# Driver.net
KiCad netlist of a schematic drawn in EAGLE
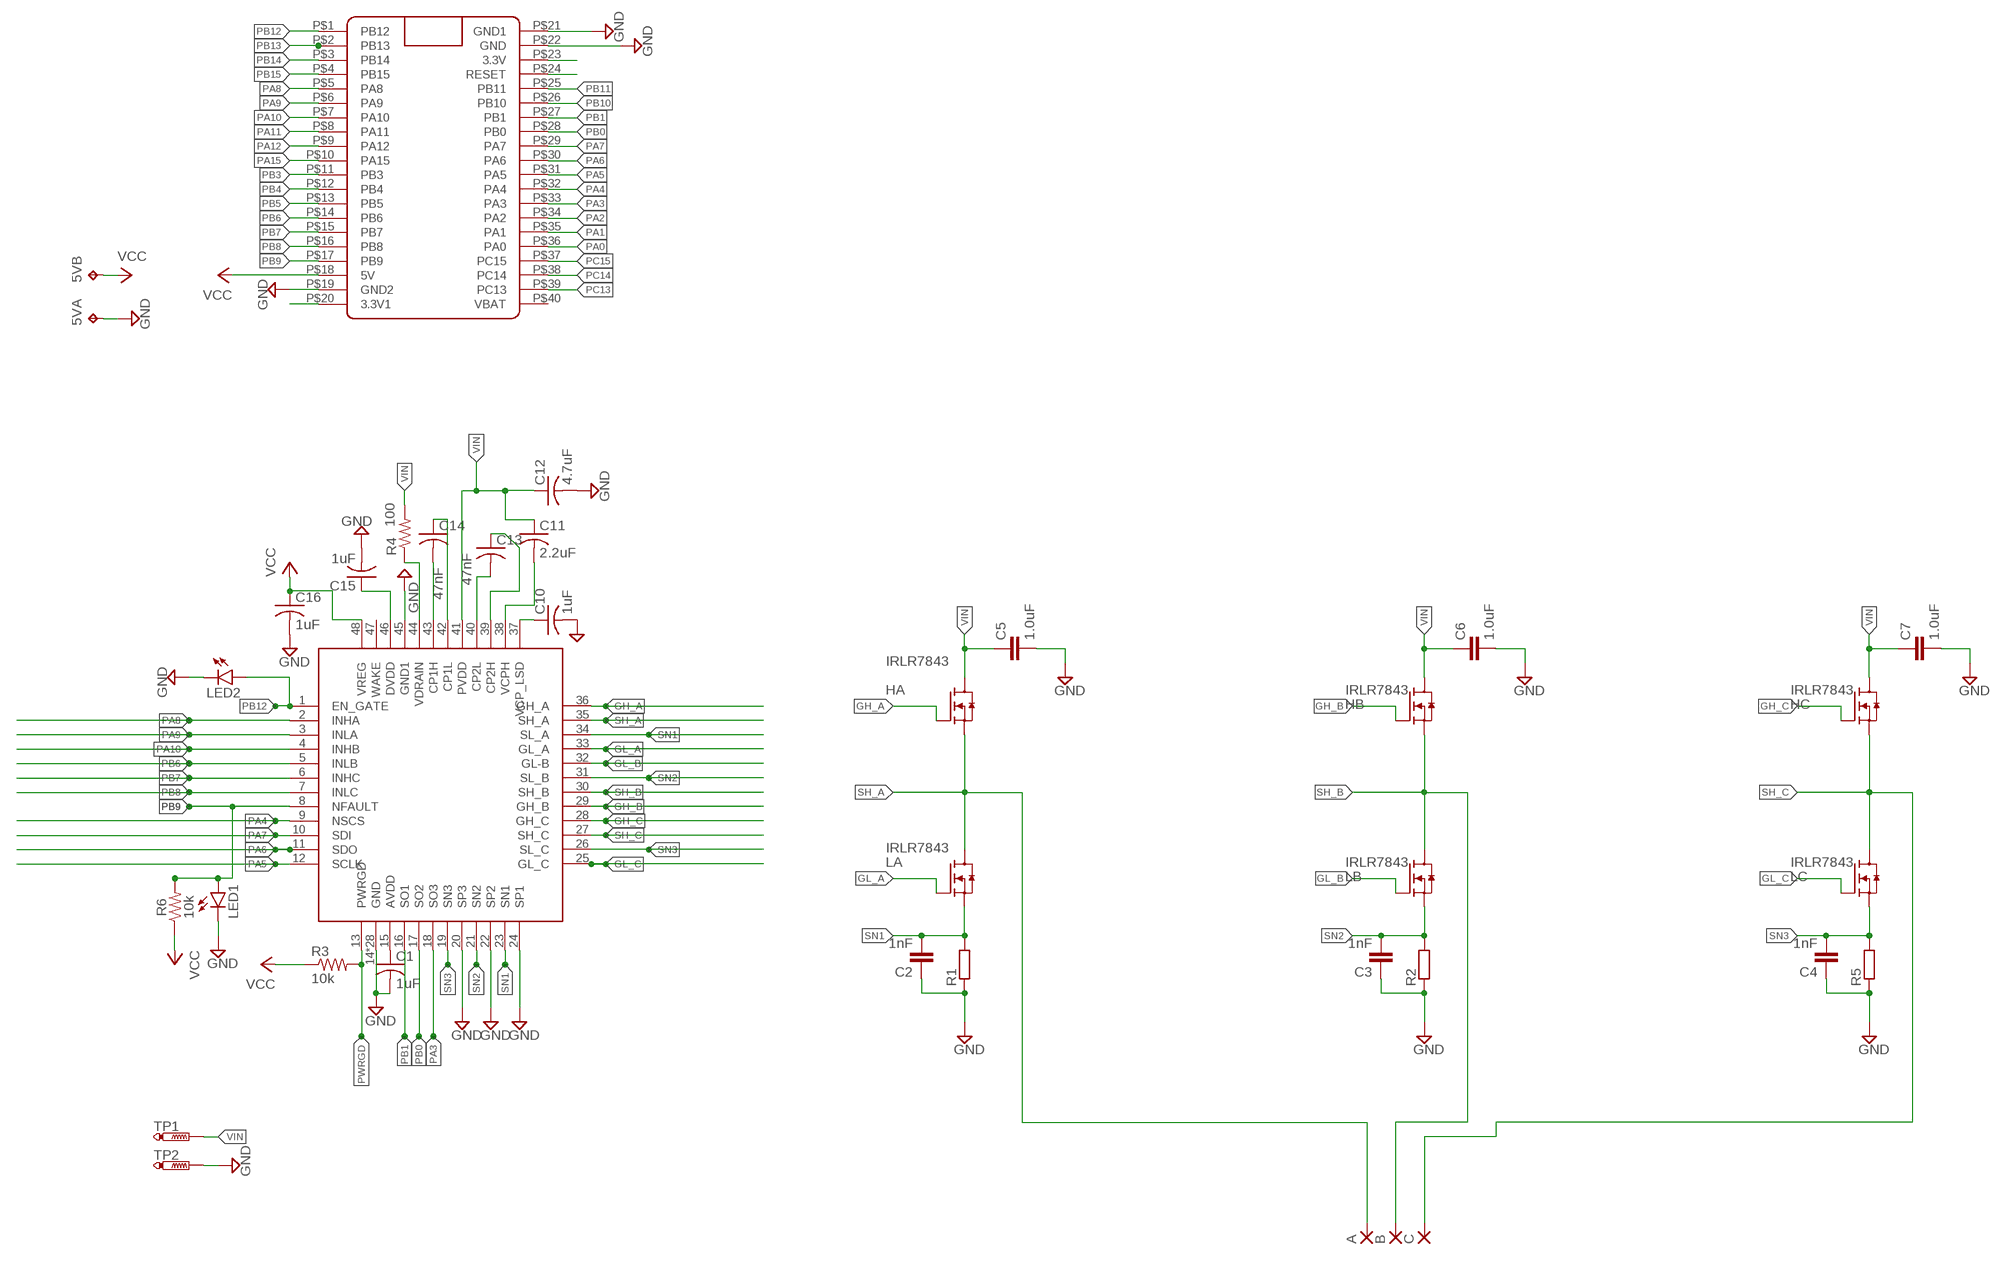
[diagram p0: schematic, sheet 1]

(export (version "E")
  (design (tool "Eeschema 10.0.6"))
  (components
    (comp (ref "5V")
      (value "TP2P2-38-17")
      (footprint "eagle-import:P2-38-17")
      (libsource (lib "eagle-import") (part "TP2P2-38-17"))
    )
    (comp (ref "A")
      (value "SMD5")
      (footprint "eagle-import:SMD2,54-5,08")
      (libsource (lib "eagle-import") (part "SMD5"))
    )
    (comp (ref "B")
      (value "SMD5")
      (footprint "eagle-import:SMD2,54-5,08")
      (libsource (lib "eagle-import") (part "SMD5"))
    )
    (comp (ref "C")
      (value "SMD5")
      (footprint "eagle-import:SMD2,54-5,08")
      (libsource (lib "eagle-import") (part "SMD5"))
    )
    (comp (ref "C1")
      (value "1uF")
      (footprint "eagle-import:C0603")
      (libsource (lib "eagle-import") (part "C-USC0603"))
    )
    (comp (ref "C2")
      (value "1nF")
      (footprint "eagle-import:0603")
      (libsource (lib "eagle-import") (part "1.0NF/1000PF-0603-50V-10%"))
    )
    (comp (ref "C3")
      (value "1nF")
      (footprint "eagle-import:0603")
      (libsource (lib "eagle-import") (part "1.0NF/1000PF-0603-50V-10%"))
    )
    (comp (ref "C4")
      (value "1nF")
      (footprint "eagle-import:0603")
      (libsource (lib "eagle-import") (part "1.0NF/1000PF-0603-50V-10%"))
    )
    (comp (ref "C5")
      (value "1.0uF")
      (footprint "eagle-import:0603")
      (libsource (lib "eagle-import") (part "1.0UF-0603-16V-10%-X7R"))
    )
    (comp (ref "C6")
      (value "1.0uF")
      (footprint "eagle-import:0603")
      (libsource (lib "eagle-import") (part "1.0UF-0603-16V-10%-X7R"))
    )
    (comp (ref "C7")
      (value "1.0uF")
      (footprint "eagle-import:0603")
      (libsource (lib "eagle-import") (part "1.0UF-0603-16V-10%-X7R"))
    )
    (comp (ref "C10")
      (value "1uF")
      (footprint "eagle-import:C0603")
      (libsource (lib "eagle-import") (part "C-USC0603"))
    )
    (comp (ref "C11")
      (value "2.2uF")
      (footprint "eagle-import:C0603")
      (libsource (lib "eagle-import") (part "C-USC0603"))
    )
    (comp (ref "C12")
      (value "4.7uF")
      (footprint "eagle-import:C0603")
      (libsource (lib "eagle-import") (part "C-USC0603"))
    )
    (comp (ref "C13")
      (value "47nF")
      (footprint "eagle-import:C0603")
      (libsource (lib "eagle-import") (part "C-USC0603"))
    )
    (comp (ref "C14")
      (value "47nF")
      (footprint "eagle-import:C0603")
      (libsource (lib "eagle-import") (part "C-USC0603"))
    )
    (comp (ref "C15")
      (value "1uF")
      (footprint "eagle-import:C0603")
      (libsource (lib "eagle-import") (part "C-USC0603"))
    )
    (comp (ref "C16")
      (value "1uF")
      (footprint "eagle-import:C0603")
      (libsource (lib "eagle-import") (part "C-USC0603"))
    )
    (comp (ref "HA")
      (value "IRLR7843")
      (footprint "eagle-import:TO252")
      (libsource (lib "eagle-import") (part "IRLR7843"))
    )
    (comp (ref "HB")
      (value "IRLR7843")
      (footprint "eagle-import:TO252")
      (libsource (lib "eagle-import") (part "IRLR7843"))
    )
    (comp (ref "HC")
      (value "IRLR7843")
      (footprint "eagle-import:TO252")
      (libsource (lib "eagle-import") (part "IRLR7843"))
    )
    (comp (ref "LA")
      (value "IRLR7843")
      (footprint "eagle-import:TO252")
      (libsource (lib "eagle-import") (part "IRLR7843"))
    )
    (comp (ref "LB")
      (value "IRLR7843")
      (footprint "eagle-import:TO252")
      (libsource (lib "eagle-import") (part "IRLR7843"))
    )
    (comp (ref "LC")
      (value "IRLR7843")
      (footprint "eagle-import:TO252")
      (libsource (lib "eagle-import") (part "IRLR7843"))
    )
    (comp (ref "LED1")
      (value "LEDCHIPLED_0805")
      (footprint "eagle-import:CHIPLED_0805")
      (libsource (lib "eagle-import") (part "LEDCHIPLED_0805"))
    )
    (comp (ref "LED2")
      (value "LEDCHIPLED_0805")
      (footprint "eagle-import:CHIPLED_0805")
      (libsource (lib "eagle-import") (part "LEDCHIPLED_0805"))
    )
    (comp (ref "R1")
      (value "R-EU_R2512")
      (footprint "eagle-import:R2512")
      (libsource (lib "eagle-import") (part "R-EU_R2512"))
    )
    (comp (ref "R2")
      (value "R-EU_R2512")
      (footprint "eagle-import:R2512")
      (libsource (lib "eagle-import") (part "R-EU_R2512"))
    )
    (comp (ref "R3")
      (value "10k")
      (footprint "eagle-import:R0603")
      (libsource (lib "eagle-import") (part "R-US_R0603"))
    )
    (comp (ref "R4")
      (value "100")
      (footprint "eagle-import:R0603")
      (libsource (lib "eagle-import") (part "R-US_R0603"))
    )
    (comp (ref "R5")
      (value "R-EU_R2512")
      (footprint "eagle-import:R2512")
      (libsource (lib "eagle-import") (part "R-EU_R2512"))
    )
    (comp (ref "R6")
      (value "10k")
      (footprint "eagle-import:0603")
      (libsource (lib "eagle-import") (part "10KOHM-0603-1/10W-1%"))
    )
    (comp (ref "TP1")
      (value "PTR1PAD1-20Y")
      (footprint "eagle-import:P1-20Y")
      (libsource (lib "eagle-import") (part "PTR1PAD1-20Y"))
    )
    (comp (ref "TP2")
      (value "PTR1PAD1-20Y")
      (footprint "eagle-import:P1-20Y")
      (libsource (lib "eagle-import") (part "PTR1PAD1-20Y"))
    )
    (comp (ref "U$1")
      (value "BLUE_PILLADVANCED")
      (footprint "eagle-import:BLUE_PILL_ADV")
      (libsource (lib "eagle-import") (part "BLUE_PILLADVANCED"))
    )
    (comp (ref "U$3")
      (value "DRV8305")
      (footprint "eagle-import:PFB_S-PQFP-G48")
      (libsource (lib "eagle-import") (part "DRV8305"))
    )
  )
  (nets
    (net (code "1") (name "GH_A") (class "Default")
      (node (ref "HA") (pin "1") (pinfunction "G_1") (pintype "passive"))
      (node (ref "U$3") (pin "36") (pinfunction "GH_A_36") (pintype "bidirectional"))
    )
    (net (code "2") (name "GH_B") (class "Default")
      (node (ref "HB") (pin "1") (pinfunction "G_1") (pintype "passive"))
      (node (ref "U$3") (pin "29") (pinfunction "GH_B_29") (pintype "bidirectional"))
    )
    (net (code "3") (name "GH_C") (class "Default")
      (node (ref "HC") (pin "1") (pinfunction "G_1") (pintype "passive"))
      (node (ref "U$3") (pin "28") (pinfunction "GH_C_28") (pintype "bidirectional"))
    )
    (net (code "4") (name "GL_A") (class "Default")
      (node (ref "LA") (pin "1") (pinfunction "G_1") (pintype "passive"))
      (node (ref "U$3") (pin "33") (pinfunction "GL_A_33") (pintype "bidirectional"))
    )
    (net (code "5") (name "GL_B") (class "Default")
      (node (ref "LB") (pin "1") (pinfunction "G_1") (pintype "passive"))
      (node (ref "U$3") (pin "32") (pinfunction "GL-B_32") (pintype "bidirectional"))
    )
    (net (code "6") (name "GL_C") (class "Default")
      (node (ref "LC") (pin "1") (pinfunction "G_1") (pintype "passive"))
      (node (ref "U$3") (pin "25") (pinfunction "GL_C_25") (pintype "bidirectional"))
    )
    (net (code "7") (name "GND") (class "Default")
      (node (ref "5V") (pin "TP-1") (pinfunction "TP_TP-1") (pintype "input"))
      (node (ref "C1") (pin "2") (pinfunction "2_2") (pintype "passive"))
      (node (ref "C10") (pin "2") (pinfunction "2_2") (pintype "passive"))
      (node (ref "C12") (pin "2") (pinfunction "2_2") (pintype "passive"))
      (node (ref "C15") (pin "2") (pinfunction "2_2") (pintype "passive"))
      (node (ref "C16") (pin "2") (pinfunction "2_2") (pintype "passive"))
      (node (ref "C2") (pin "1") (pinfunction "1_1") (pintype "passive"))
      (node (ref "C3") (pin "1") (pinfunction "1_1") (pintype "passive"))
      (node (ref "C4") (pin "1") (pinfunction "1_1") (pintype "passive"))
      (node (ref "C5") (pin "2") (pinfunction "2_2") (pintype "passive"))
      (node (ref "C6") (pin "2") (pinfunction "2_2") (pintype "passive"))
      (node (ref "C7") (pin "2") (pinfunction "2_2") (pintype "passive"))
      (node (ref "LED1") (pin "C") (pinfunction "C_C") (pintype "passive"))
      (node (ref "LED2") (pin "C") (pinfunction "C_C") (pintype "passive"))
      (node (ref "R1") (pin "1") (pinfunction "1_1") (pintype "passive"))
      (node (ref "R2") (pin "1") (pinfunction "1_1") (pintype "passive"))
      (node (ref "R5") (pin "1") (pinfunction "1_1") (pintype "passive"))
      (node (ref "TP2") (pin "TP") (pinfunction "TP_TP") (pintype "input"))
      (node (ref "U$1") (pin "P$19") (pinfunction "GND2_P$19") (pintype "bidirectional"))
      (node (ref "U$1") (pin "P$21") (pinfunction "GND1_P$21") (pintype "power_in"))
      (node (ref "U$1") (pin "P$22") (pinfunction "GND_P$22") (pintype "bidirectional"))
      (node (ref "U$3") (pin "14") (pinfunction "GND_14") (pintype "bidirectional"))
      (node (ref "U$3") (pin "20") (pinfunction "SP3_20") (pintype "bidirectional"))
      (node (ref "U$3") (pin "22") (pinfunction "SP2_22") (pintype "bidirectional"))
      (node (ref "U$3") (pin "24") (pinfunction "SP1_24") (pintype "bidirectional"))
      (node (ref "U$3") (pin "45") (pinfunction "GND1_45") (pintype "bidirectional"))
      (node (ref "U$3") (pin "P$1") (pinfunction "GND_P$1") (pintype "bidirectional"))
      (node (ref "U$3") (pin "P$10") (pinfunction "GND_P$10") (pintype "bidirectional"))
      (node (ref "U$3") (pin "P$11") (pinfunction "GND_P$11") (pintype "bidirectional"))
      (node (ref "U$3") (pin "P$12") (pinfunction "GND_P$12") (pintype "bidirectional"))
      (node (ref "U$3") (pin "P$13") (pinfunction "GND_P$13") (pintype "bidirectional"))
      (node (ref "U$3") (pin "P$14") (pinfunction "GND_P$14") (pintype "bidirectional"))
      (node (ref "U$3") (pin "P$15") (pinfunction "GND_P$15") (pintype "bidirectional"))
      (node (ref "U$3") (pin "P$16") (pinfunction "GND_P$16") (pintype "bidirectional"))
      (node (ref "U$3") (pin "P$17") (pinfunction "GND_P$17") (pintype "bidirectional"))
      (node (ref "U$3") (pin "P$18") (pinfunction "GND_P$18") (pintype "bidirectional"))
      (node (ref "U$3") (pin "P$19") (pinfunction "GND_P$19") (pintype "bidirectional"))
      (node (ref "U$3") (pin "P$2") (pinfunction "GND_P$2") (pintype "bidirectional"))
      (node (ref "U$3") (pin "P$20") (pinfunction "GND_P$20") (pintype "bidirectional"))
      (node (ref "U$3") (pin "P$21") (pinfunction "GND_P$21") (pintype "bidirectional"))
      (node (ref "U$3") (pin "P$22") (pinfunction "GND_P$22") (pintype "bidirectional"))
      (node (ref "U$3") (pin "P$23") (pinfunction "GND_P$23") (pintype "bidirectional"))
      (node (ref "U$3") (pin "P$24") (pinfunction "GND_P$24") (pintype "bidirectional"))
      (node (ref "U$3") (pin "P$25") (pinfunction "GND_P$25") (pintype "bidirectional"))
      (node (ref "U$3") (pin "P$26") (pinfunction "GND_P$26") (pintype "bidirectional"))
      (node (ref "U$3") (pin "P$27") (pinfunction "GND_P$27") (pintype "bidirectional"))
      (node (ref "U$3") (pin "P$3") (pinfunction "GND_P$3") (pintype "bidirectional"))
      (node (ref "U$3") (pin "P$4") (pinfunction "GND_P$4") (pintype "bidirectional"))
      (node (ref "U$3") (pin "P$5") (pinfunction "GND_P$5") (pintype "bidirectional"))
      (node (ref "U$3") (pin "P$6") (pinfunction "GND_P$6") (pintype "bidirectional"))
      (node (ref "U$3") (pin "P$7") (pinfunction "GND_P$7") (pintype "bidirectional"))
      (node (ref "U$3") (pin "P$8") (pinfunction "GND_P$8") (pintype "bidirectional"))
      (node (ref "U$3") (pin "P$9") (pinfunction "GND_P$9") (pintype "bidirectional"))
    )
    (net (code "8") (name "Net-(U$3-AVDD)") (class "Default")
      (node (ref "C1") (pin "1") (pinfunction "1_1") (pintype "passive"))
      (node (ref "U$3") (pin "15") (pinfunction "AVDD_15") (pintype "bidirectional"))
    )
    (net (code "9") (name "Net-(U$3-CP1H)") (class "Default")
      (node (ref "C14") (pin "2") (pinfunction "2_2") (pintype "passive"))
      (node (ref "U$3") (pin "43") (pinfunction "CP1H_43") (pintype "bidirectional"))
    )
    (net (code "10") (name "Net-(U$3-CP1L)") (class "Default")
      (node (ref "C14") (pin "1") (pinfunction "1_1") (pintype "passive"))
      (node (ref "U$3") (pin "42") (pinfunction "CP1L_42") (pintype "bidirectional"))
    )
    (net (code "11") (name "Net-(U$3-CP2H)") (class "Default")
      (node (ref "C13") (pin "1") (pinfunction "1_1") (pintype "passive"))
      (node (ref "U$3") (pin "39") (pinfunction "CP2H_39") (pintype "bidirectional"))
    )
    (net (code "12") (name "Net-(U$3-CP2L)") (class "Default")
      (node (ref "C13") (pin "2") (pinfunction "2_2") (pintype "passive"))
      (node (ref "U$3") (pin "40") (pinfunction "CP2L_40") (pintype "bidirectional"))
    )
    (net (code "13") (name "Net-(U$3-DVDD)") (class "Default")
      (node (ref "C15") (pin "1") (pinfunction "1_1") (pintype "passive"))
      (node (ref "U$3") (pin "46") (pinfunction "DVDD_46") (pintype "bidirectional"))
    )
    (net (code "14") (name "Net-(U$3-VCPH)") (class "Default")
      (node (ref "C11") (pin "2") (pinfunction "2_2") (pintype "passive"))
      (node (ref "U$3") (pin "38") (pinfunction "VCPH_38") (pintype "bidirectional"))
    )
    (net (code "15") (name "Net-(U$3-VCP_LSD)") (class "Default")
      (node (ref "C10") (pin "1") (pinfunction "1_1") (pintype "passive"))
      (node (ref "U$3") (pin "37") (pinfunction "VCP_LSD_37") (pintype "bidirectional"))
    )
    (net (code "16") (name "Net-(U$3-VDRAIN)") (class "Default")
      (node (ref "R4") (pin "1") (pinfunction "1_1") (pintype "passive"))
      (node (ref "U$3") (pin "44") (pinfunction "VDRAIN_44") (pintype "bidirectional"))
    )
    (net (code "17") (name "PA0") (class "Default")
      (node (ref "U$1") (pin "P$36") (pinfunction "PA0_P$36") (pintype "bidirectional"))
    )
    (net (code "18") (name "PA1") (class "Default")
      (node (ref "U$1") (pin "P$35") (pinfunction "PA1_P$35") (pintype "bidirectional"))
    )
    (net (code "19") (name "PA2") (class "Default")
      (node (ref "U$1") (pin "P$34") (pinfunction "PA2_P$34") (pintype "bidirectional"))
    )
    (net (code "20") (name "PA3") (class "Default")
      (node (ref "U$1") (pin "P$33") (pinfunction "PA3_P$33") (pintype "bidirectional"))
      (node (ref "U$3") (pin "18") (pinfunction "SO3_18") (pintype "bidirectional"))
    )
    (net (code "21") (name "PA4") (class "Default")
      (node (ref "U$1") (pin "P$32") (pinfunction "PA4_P$32") (pintype "bidirectional"))
      (node (ref "U$3") (pin "9") (pinfunction "NSCS_9") (pintype "bidirectional"))
    )
    (net (code "22") (name "PA5") (class "Default")
      (node (ref "U$1") (pin "P$31") (pinfunction "PA5_P$31") (pintype "bidirectional"))
      (node (ref "U$3") (pin "12") (pinfunction "SCLK_12") (pintype "bidirectional"))
    )
    (net (code "23") (name "PA6") (class "Default")
      (node (ref "U$1") (pin "P$30") (pinfunction "PA6_P$30") (pintype "bidirectional"))
      (node (ref "U$3") (pin "11") (pinfunction "SDO_11") (pintype "bidirectional"))
    )
    (net (code "24") (name "PA7") (class "Default")
      (node (ref "U$1") (pin "P$29") (pinfunction "PA7_P$29") (pintype "bidirectional"))
      (node (ref "U$3") (pin "10") (pinfunction "SDI_10") (pintype "bidirectional"))
    )
    (net (code "25") (name "PA8") (class "Default")
      (node (ref "U$1") (pin "P$5") (pinfunction "PA8_P$5") (pintype "bidirectional"))
      (node (ref "U$3") (pin "2") (pinfunction "INHA_2") (pintype "bidirectional"))
    )
    (net (code "26") (name "PA9") (class "Default")
      (node (ref "U$1") (pin "P$6") (pinfunction "PA9_P$6") (pintype "bidirectional"))
      (node (ref "U$3") (pin "3") (pinfunction "INLA_3") (pintype "bidirectional"))
    )
    (net (code "27") (name "PA10") (class "Default")
      (node (ref "U$1") (pin "P$7") (pinfunction "PA10_P$7") (pintype "bidirectional"))
      (node (ref "U$3") (pin "4") (pinfunction "INHB_4") (pintype "bidirectional"))
    )
    (net (code "28") (name "PA11") (class "Default")
      (node (ref "U$1") (pin "P$8") (pinfunction "PA11_P$8") (pintype "bidirectional"))
    )
    (net (code "29") (name "PA12") (class "Default")
      (node (ref "U$1") (pin "P$9") (pinfunction "PA12_P$9") (pintype "bidirectional"))
    )
    (net (code "30") (name "PA15") (class "Default")
      (node (ref "U$1") (pin "P$10") (pinfunction "PA15_P$10") (pintype "bidirectional"))
    )
    (net (code "31") (name "PB0") (class "Default")
      (node (ref "U$1") (pin "P$28") (pinfunction "PB0_P$28") (pintype "bidirectional"))
      (node (ref "U$3") (pin "17") (pinfunction "SO2_17") (pintype "bidirectional"))
    )
    (net (code "32") (name "PB1") (class "Default")
      (node (ref "U$1") (pin "P$27") (pinfunction "PB1_P$27") (pintype "bidirectional"))
      (node (ref "U$3") (pin "16") (pinfunction "SO1_16") (pintype "bidirectional"))
    )
    (net (code "33") (name "PB3") (class "Default")
      (node (ref "U$1") (pin "P$11") (pinfunction "PB3_P$11") (pintype "bidirectional"))
    )
    (net (code "34") (name "PB4") (class "Default")
      (node (ref "U$1") (pin "P$12") (pinfunction "PB4_P$12") (pintype "bidirectional"))
    )
    (net (code "35") (name "PB5") (class "Default")
      (node (ref "U$1") (pin "P$13") (pinfunction "PB5_P$13") (pintype "bidirectional"))
    )
    (net (code "36") (name "PB6") (class "Default")
      (node (ref "U$1") (pin "P$14") (pinfunction "PB6_P$14") (pintype "bidirectional"))
      (node (ref "U$3") (pin "5") (pinfunction "INLB_5") (pintype "bidirectional"))
    )
    (net (code "37") (name "PB7") (class "Default")
      (node (ref "U$1") (pin "P$15") (pinfunction "PB7_P$15") (pintype "bidirectional"))
      (node (ref "U$3") (pin "6") (pinfunction "INHC_6") (pintype "bidirectional"))
    )
    (net (code "38") (name "PB8") (class "Default")
      (node (ref "U$1") (pin "P$16") (pinfunction "PB8_P$16") (pintype "bidirectional"))
      (node (ref "U$3") (pin "7") (pinfunction "INLC_7") (pintype "bidirectional"))
    )
    (net (code "39") (name "PB9") (class "Default")
      (node (ref "LED1") (pin "A") (pinfunction "A_A") (pintype "passive"))
      (node (ref "R6") (pin "2") (pinfunction "2_2") (pintype "passive"))
      (node (ref "U$1") (pin "P$17") (pinfunction "PB9_P$17") (pintype "bidirectional"))
      (node (ref "U$3") (pin "8") (pinfunction "NFAULT_8") (pintype "bidirectional"))
    )
    (net (code "40") (name "PB10") (class "Default")
      (node (ref "U$1") (pin "P$26") (pinfunction "PB10_P$26") (pintype "bidirectional"))
    )
    (net (code "41") (name "PB11") (class "Default")
      (node (ref "U$1") (pin "P$25") (pinfunction "PB11_P$25") (pintype "bidirectional"))
    )
    (net (code "42") (name "PB12") (class "Default")
      (node (ref "LED2") (pin "A") (pinfunction "A_A") (pintype "passive"))
      (node (ref "U$1") (pin "P$1") (pinfunction "PB12_P$1") (pintype "bidirectional"))
      (node (ref "U$3") (pin "1") (pinfunction "EN_GATE_1") (pintype "bidirectional"))
    )
    (net (code "43") (name "PB13") (class "Default")
      (node (ref "U$1") (pin "P$2") (pinfunction "PB13_P$2") (pintype "bidirectional"))
    )
    (net (code "44") (name "PB14") (class "Default")
      (node (ref "U$1") (pin "P$3") (pinfunction "PB14_P$3") (pintype "bidirectional"))
    )
    (net (code "45") (name "PB15") (class "Default")
      (node (ref "U$1") (pin "P$4") (pinfunction "PB15_P$4") (pintype "bidirectional"))
    )
    (net (code "46") (name "PC13") (class "Default")
      (node (ref "U$1") (pin "P$39") (pinfunction "PC13_P$39") (pintype "bidirectional"))
    )
    (net (code "47") (name "PC14") (class "Default")
      (node (ref "U$1") (pin "P$38") (pinfunction "PC14_P$38") (pintype "bidirectional"))
    )
    (net (code "48") (name "PC15") (class "Default")
      (node (ref "U$1") (pin "P$37") (pinfunction "PC15_P$37") (pintype "bidirectional"))
    )
    (net (code "49") (name "PWRGD") (class "Default")
      (node (ref "R3") (pin "2") (pinfunction "2_2") (pintype "passive"))
      (node (ref "U$3") (pin "13") (pinfunction "PWRGD_13") (pintype "bidirectional"))
    )
    (net (code "50") (name "SH_A") (class "Default")
      (node (ref "A") (pin "1") (pinfunction "P_1") (pintype "passive"))
      (node (ref "HA") (pin "2") (pinfunction "S_2") (pintype "passive"))
      (node (ref "LA") (pin "3") (pinfunction "D_3") (pintype "passive"))
      (node (ref "U$3") (pin "35") (pinfunction "SH_A_35") (pintype "bidirectional"))
    )
    (net (code "51") (name "SH_B") (class "Default")
      (node (ref "B") (pin "1") (pinfunction "P_1") (pintype "passive"))
      (node (ref "HB") (pin "2") (pinfunction "S_2") (pintype "passive"))
      (node (ref "LB") (pin "3") (pinfunction "D_3") (pintype "passive"))
      (node (ref "U$3") (pin "30") (pinfunction "SH_B_30") (pintype "bidirectional"))
    )
    (net (code "52") (name "SH_C") (class "Default")
      (node (ref "C") (pin "1") (pinfunction "P_1") (pintype "passive"))
      (node (ref "HC") (pin "2") (pinfunction "S_2") (pintype "passive"))
      (node (ref "LC") (pin "3") (pinfunction "D_3") (pintype "passive"))
      (node (ref "U$3") (pin "27") (pinfunction "SH_C_27") (pintype "bidirectional"))
    )
    (net (code "53") (name "SN1") (class "Default")
      (node (ref "C2") (pin "2") (pinfunction "2_2") (pintype "passive"))
      (node (ref "LA") (pin "2") (pinfunction "S_2") (pintype "passive"))
      (node (ref "R1") (pin "2") (pinfunction "2_2") (pintype "passive"))
      (node (ref "U$3") (pin "23") (pinfunction "SN1_23") (pintype "bidirectional"))
      (node (ref "U$3") (pin "34") (pinfunction "SL_A_34") (pintype "bidirectional"))
    )
    (net (code "54") (name "SN2") (class "Default")
      (node (ref "C3") (pin "2") (pinfunction "2_2") (pintype "passive"))
      (node (ref "LB") (pin "2") (pinfunction "S_2") (pintype "passive"))
      (node (ref "R2") (pin "2") (pinfunction "2_2") (pintype "passive"))
      (node (ref "U$3") (pin "21") (pinfunction "SN2_21") (pintype "bidirectional"))
      (node (ref "U$3") (pin "31") (pinfunction "SL_B_31") (pintype "bidirectional"))
    )
    (net (code "55") (name "SN3") (class "Default")
      (node (ref "C4") (pin "2") (pinfunction "2_2") (pintype "passive"))
      (node (ref "LC") (pin "2") (pinfunction "S_2") (pintype "passive"))
      (node (ref "R5") (pin "2") (pinfunction "2_2") (pintype "passive"))
      (node (ref "U$3") (pin "19") (pinfunction "SN3_19") (pintype "bidirectional"))
      (node (ref "U$3") (pin "26") (pinfunction "SL_C_26") (pintype "bidirectional"))
    )
    (net (code "56") (name "VCC") (class "Default")
      (node (ref "5V") (pin "TP-2") (pinfunction "TP_TP-2") (pintype "input"))
      (node (ref "C16") (pin "1") (pinfunction "1_1") (pintype "passive"))
      (node (ref "R3") (pin "1") (pinfunction "1_1") (pintype "passive"))
      (node (ref "R6") (pin "1") (pinfunction "1_1") (pintype "passive"))
      (node (ref "U$1") (pin "P$18") (pinfunction "5V_P$18") (pintype "bidirectional"))
      (node (ref "U$3") (pin "48") (pinfunction "VREG_48") (pintype "bidirectional"))
    )
    (net (code "57") (name "VIN") (class "Default")
      (node (ref "C11") (pin "1") (pinfunction "1_1") (pintype "passive"))
      (node (ref "C12") (pin "1") (pinfunction "1_1") (pintype "passive"))
      (node (ref "C5") (pin "1") (pinfunction "1_1") (pintype "passive"))
      (node (ref "C6") (pin "1") (pinfunction "1_1") (pintype "passive"))
      (node (ref "C7") (pin "1") (pinfunction "1_1") (pintype "passive"))
      (node (ref "HA") (pin "3") (pinfunction "D_3") (pintype "passive"))
      (node (ref "HB") (pin "3") (pinfunction "D_3") (pintype "passive"))
      (node (ref "HC") (pin "3") (pinfunction "D_3") (pintype "passive"))
      (node (ref "R4") (pin "2") (pinfunction "2_2") (pintype "passive"))
      (node (ref "TP1") (pin "TP") (pinfunction "TP_TP") (pintype "input"))
      (node (ref "U$3") (pin "41") (pinfunction "PVDD_41") (pintype "bidirectional"))
    )
    (net (code "58") (name "unconnected-(U$1-3.3V-PadP$23)") (class "Default")
      (node (ref "U$1") (pin "P$23") (pinfunction "3.3V_P$23") (pintype "bidirectional"))
    )
    (net (code "59") (name "unconnected-(U$1-3.3V1-PadP$20)") (class "Default")
      (node (ref "U$1") (pin "P$20") (pinfunction "3.3V1_P$20") (pintype "bidirectional"))
    )
    (net (code "60") (name "unconnected-(U$1-RESET-PadP$24)") (class "Default")
      (node (ref "U$1") (pin "P$24") (pinfunction "RESET_P$24") (pintype "bidirectional"))
    )
    (net (code "61") (name "unconnected-(U$1-VBAT-PadP$40)") (class "Default")
      (node (ref "U$1") (pin "P$40") (pinfunction "VBAT_P$40") (pintype "bidirectional"))
    )
    (net (code "62") (name "unconnected-(U$3-WAKE-Pad47)") (class "Default")
      (node (ref "U$3") (pin "47") (pinfunction "WAKE_47") (pintype "bidirectional"))
    )
  )
)
